# Sheet1.net
KiCad netlist of a schematic drawn in Altium Designer
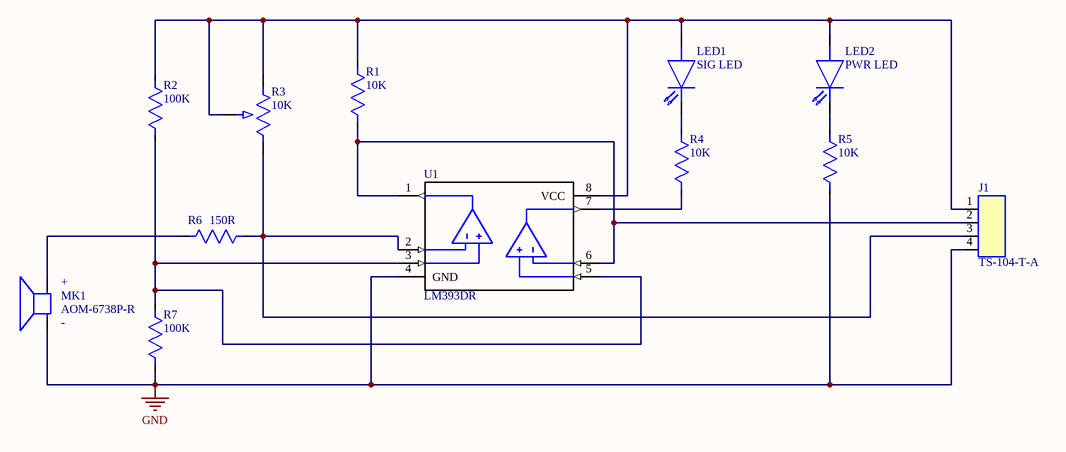
[diagram p0: Sheet1.SchDoc]

(export (version "E")
  (design (tool "Eeschema 10.0.6"))
  (components
    (comp (ref "J1")
      (value "TS-104-T-A")
      (footprint "TS-104-T-A")
      (description "CONN HEADER VERT 4POS 2.54MM")
      (libsource (lib "Integrated_Library1") (part "TS-104-T-A"))
    )
    (comp (ref "LED1")
      (value "SIG LED")
      (footprint "CMD15-21VRD/TR8")
      (description "Red LED Indication - Discrete 1.7V 1206 (3216 Metric)")
      (libsource (lib "Integrated_Library1") (part "CMD15-21VRDTR8"))
    )
    (comp (ref "LED2")
      (value "PWR LED")
      (footprint "CMD15-21VRD/TR8")
      (description "Red LED Indication - Discrete 1.7V 1206 (3216 Metric)")
      (libsource (lib "Integrated_Library1") (part "CMD15-21VRDTR8"))
    )
    (comp (ref "MK1")
      (value "AOM-6738P-R")
      (footprint "AOM-6738P-R")
      (libsource (lib "Integrated_Library1") (part "AOM-6738P-R"))
    )
    (comp (ref "R1")
      (value "10K")
      (footprint "ERJ-6GEYJ103V")
      (description "10 kOhms ±5% 0.125W, 1/8W Chip Resistor 0805 (2012 Metric) Automotive AEC-Q200 Thick Film")
      (libsource (lib "Integrated_Library1") (part "ERJ-6GEYJ103V"))
    )
    (comp (ref "R2")
      (value "100K")
      (footprint "RC0805JR-07100KL")
      (description "100 kOhms ±5% 0.125W, 1/8W Chip Resistor 0805 (2012 Metric) Moisture Resistant Thick Film")
      (libsource (lib "Integrated_Library1") (part "RC0805JR-07100KL"))
    )
    (comp (ref "R3")
      (value "10K")
      (footprint "3296W-1-103LF")
      (description "10 kOhms 0.5W, 1/2W PC Pins Through Hole Trimmer Potentiometer Cermet 25.0 Turn Top Adjustment")
      (libsource (lib "Integrated_Library1") (part "3296W-1-103LF"))
    )
    (comp (ref "R4")
      (value "10K")
      (footprint "ERJ-6GEYJ103V")
      (description "10 kOhms ±5% 0.125W, 1/8W Chip Resistor 0805 (2012 Metric) Automotive AEC-Q200 Thick Film")
      (libsource (lib "Integrated_Library1") (part "ERJ-6GEYJ103V"))
    )
    (comp (ref "R5")
      (value "10K")
      (footprint "ERJ-6GEYJ103V")
      (description "10 kOhms ±5% 0.125W, 1/8W Chip Resistor 0805 (2012 Metric) Automotive AEC-Q200 Thick Film")
      (libsource (lib "Integrated_Library1") (part "ERJ-6GEYJ103V"))
    )
    (comp (ref "R6")
      (value "150R")
      (footprint "RC0805JR-07150RL")
      (description "150 Ohms ±5% 0.125W, 1/8W Chip Resistor 0805 (2012 Metric) Moisture Resistant Thick Film")
      (libsource (lib "Integrated_Library1") (part "RC0805JR-07150RL"))
    )
    (comp (ref "R7")
      (value "100K")
      (footprint "RC0805JR-07100KL")
      (description "100 kOhms ±5% 0.125W, 1/8W Chip Resistor 0805 (2012 Metric) Moisture Resistant Thick Film")
      (libsource (lib "Integrated_Library1") (part "RC0805JR-07100KL"))
    )
    (comp (ref "U1")
      (value "LM393DR")
      (footprint "LM393DR")
      (description "IC COMPARATOR 2 DIFF 8SOIC")
      (libsource (lib "Integrated_Library1") (part "LM393DR"))
    )
  )
  (nets
    (net (code "1") (name "GND") (class "Default")
      (node (ref "J1") (pin "4") (pinfunction "4_4") (pintype "passive"))
      (node (ref "MK1") (pin "N") (pinfunction "NEG_N") (pintype "passive"))
      (node (ref "R5") (pin "1") (pinfunction "1_1") (pintype "passive"))
      (node (ref "R7") (pin "1") (pinfunction "1_1") (pintype "passive"))
      (node (ref "U1") (pin "4") (pinfunction "GND_4") (pintype "power_in"))
    )
    (net (code "2") (name "Net-(LED1-Pad2)") (class "Default")
      (node (ref "LED1") (pin "2") (pinfunction "2_2") (pintype "passive"))
      (node (ref "R4") (pin "2") (pinfunction "2_2") (pintype "passive"))
    )
    (net (code "3") (name "Net-(LED2-Pad2)") (class "Default")
      (node (ref "LED2") (pin "2") (pinfunction "2_2") (pintype "passive"))
      (node (ref "R5") (pin "2") (pinfunction "2_2") (pintype "passive"))
    )
    (net (code "4") (name "Net-(MK1-POS)") (class "Default")
      (node (ref "MK1") (pin "P") (pinfunction "POS_P") (pintype "passive"))
      (node (ref "R6") (pin "1") (pinfunction "1_1") (pintype "passive"))
    )
    (net (code "5") (name "Net-(U1-1IN+)") (class "Default")
      (node (ref "R2") (pin "1") (pinfunction "1_1") (pintype "passive"))
      (node (ref "R7") (pin "2") (pinfunction "2_2") (pintype "passive"))
      (node (ref "U1") (pin "3") (pinfunction "1IN+_3") (pintype "input"))
      (node (ref "U1") (pin "5") (pinfunction "2IN+_5") (pintype "input"))
    )
    (net (code "6") (name "Net-(U1-1IN-)") (class "Default")
      (node (ref "J1") (pin "3") (pinfunction "3_3") (pintype "passive"))
      (node (ref "R3") (pin "1") (pinfunction "1_1") (pintype "passive"))
      (node (ref "R6") (pin "2") (pinfunction "2_2") (pintype "passive"))
      (node (ref "U1") (pin "2") (pinfunction "1IN-_2") (pintype "input"))
    )
    (net (code "7") (name "Net-(U1-2IN-)") (class "Default")
      (node (ref "J1") (pin "2") (pinfunction "2_2") (pintype "passive"))
      (node (ref "R1") (pin "1") (pinfunction "1_1") (pintype "passive"))
      (node (ref "U1") (pin "1") (pinfunction "OUT1_1") (pintype "output"))
      (node (ref "U1") (pin "6") (pinfunction "2IN-_6") (pintype "input"))
    )
    (net (code "8") (name "Net-(U1-OUT2)") (class "Default")
      (node (ref "R4") (pin "1") (pinfunction "1_1") (pintype "passive"))
      (node (ref "U1") (pin "7") (pinfunction "OUT2_7") (pintype "output"))
    )
    (net (code "9") (name "Net-(U1-VCC)") (class "Default")
      (node (ref "J1") (pin "1") (pinfunction "1_1") (pintype "passive"))
      (node (ref "LED1") (pin "1") (pinfunction "1_1") (pintype "passive"))
      (node (ref "LED2") (pin "1") (pinfunction "1_1") (pintype "passive"))
      (node (ref "R1") (pin "2") (pinfunction "2_2") (pintype "passive"))
      (node (ref "R2") (pin "2") (pinfunction "2_2") (pintype "passive"))
      (node (ref "R3") (pin "2") (pinfunction "2_2") (pintype "passive"))
      (node (ref "R3") (pin "3") (pinfunction "3_3") (pintype "passive"))
      (node (ref "U1") (pin "8") (pinfunction "VCC_8") (pintype "power_in"))
    )
  )
)
